# Schematic.net
KiCad netlist of a schematic drawn in Altium Designer
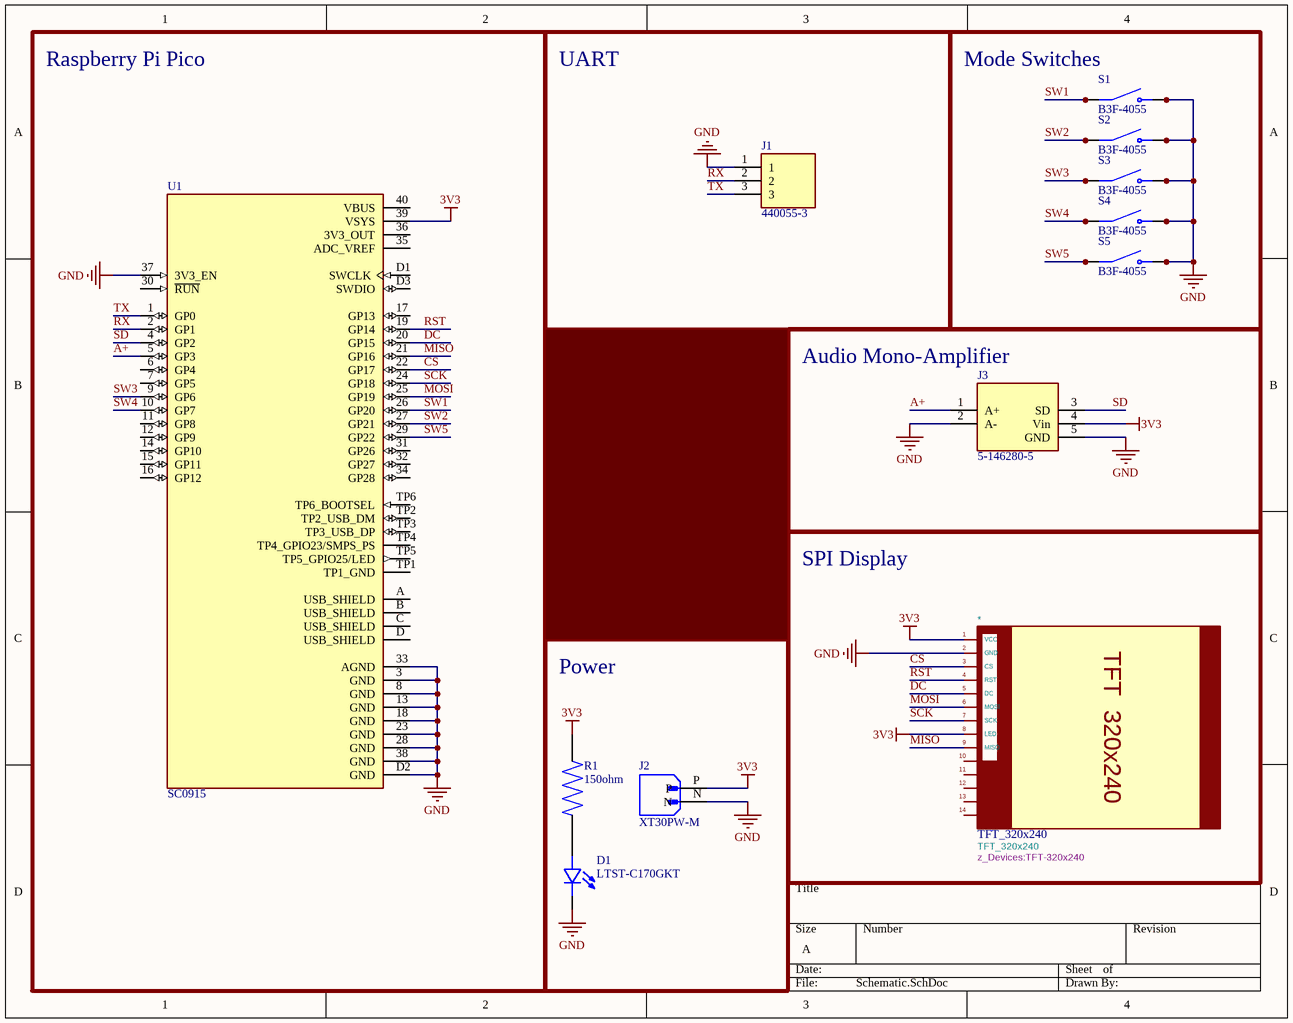
[diagram p0: Schematic.SchDoc]

(export (version "E")
  (design (tool "Eeschema 10.0.6"))
  (components
    (comp (ref "*")
      (value "TFT_320x240")
      (footprint "z_Devices:TFT-320x240")
      (fields (field (name "ALTIUM_VALUE") "TFT_320x240"))
      (libsource (lib "2.8inch") (part "TFT_320x240"))
    )
    (comp (ref "D1")
      (value "LTST-C170GKT")
      (footprint "LED_LTST-C170GKT")
      (description "Green 569nm LED Indication - Discrete 2.1V 0805 (2012 Metric)")
      (fields (field (name "MF") "Lite-On Inc."))
      (libsource (lib "LTST-C170GKT") (part "LTST-C170GKT"))
    )
    (comp (ref "J1")
      (value "440055-3")
      (footprint "TE_440055-3")
      (description "Connector Header Through Hole, Right Angle 3 position 0.079 _2.00mm_")
      (fields (field (name "MF") "TE Connectivity") (field (name "DIGI-KEY_PART_NUMBER") "A100044-ND"))
      (libsource (lib "440055-3") (part "440055-3"))
    )
    (comp (ref "J2")
      (value "XT30PW-M")
      (footprint "AMASS_XT30PW-M")
      (description "Socket; DC supply; XT30; male; PIN: 2; on PCBs; THT; Colour: yellow")
      (fields (field (name "MF") "AMASS"))
      (libsource (lib "XT30PW-M") (part "XT30PW-M"))
    )
    (comp (ref "J3")
      (value "5-146280-5")
      (footprint "TE_5-146280-5")
      (description "05 MODII HDR SRST B/A .100CL")
      (libsource (lib "5-146280-5 (2)") (part "5-146280-5"))
    )
    (comp (ref "R1")
      (value "150ohm")
      (footprint "RESC1005X40N")
      (description "150 Ohms Â±1% 0.063W, 1/16W Chip Resistor 0402 (1005 Metric) Moisture Resistant Thick Film")
      (fields (field (name "MF") "Yageo") (field (name "MP") "RC0402FR-07150RL"))
      (libsource (lib "RC0402FR-07150RL") (part "RC0402FR-07150RL"))
    )
    (comp (ref "S1")
      (value "B3F-4055")
      (footprint "SW_B3F-4055")
      (libsource (lib "B3F-4055") (part "B3F-4055"))
    )
    (comp (ref "S2")
      (value "B3F-4055")
      (footprint "SW_B3F-4055")
      (libsource (lib "B3F-4055") (part "B3F-4055"))
    )
    (comp (ref "S3")
      (value "B3F-4055")
      (footprint "SW_B3F-4055")
      (libsource (lib "B3F-4055") (part "B3F-4055"))
    )
    (comp (ref "S4")
      (value "B3F-4055")
      (footprint "SW_B3F-4055")
      (libsource (lib "B3F-4055") (part "B3F-4055"))
    )
    (comp (ref "S5")
      (value "B3F-4055")
      (footprint "SW_B3F-4055")
      (libsource (lib "B3F-4055") (part "B3F-4055"))
    )
    (comp (ref "U1")
      (value "SC0915")
      (footprint "MODULE_SC0915")
      (description "RP2040 Raspberry Pi Pico series ARMÂ® CortexÂ®-M0+ MCU 32-Bit Embedded Evaluation Board")
      (fields (field (name "MF") "Raspberry Pi"))
      (libsource (lib "SC0915") (part "SC0915"))
    )
  )
  (nets
    (net (code "1") (name "/A+") (class "Default")
      (node (ref "J3") (pin "1") (pinfunction "A+_1") (pintype "passive"))
      (node (ref "U1") (pin "5") (pinfunction "GP3_5") (pintype "bidirectional"))
    )
    (net (code "2") (name "/CS") (class "Default")
      (node (ref "*") (pin "3") (pinfunction "CS_3") (pintype "passive"))
      (node (ref "U1") (pin "22") (pinfunction "GP17_22") (pintype "bidirectional"))
    )
    (net (code "3") (name "/DC") (class "Default")
      (node (ref "*") (pin "5") (pinfunction "DC_5") (pintype "passive"))
      (node (ref "U1") (pin "20") (pinfunction "GP15_20") (pintype "bidirectional"))
    )
    (net (code "4") (name "/MISO") (class "Default")
      (node (ref "*") (pin "9") (pinfunction "MISO_9") (pintype "passive"))
      (node (ref "U1") (pin "21") (pinfunction "GP16_21") (pintype "bidirectional"))
    )
    (net (code "5") (name "/MOSI") (class "Default")
      (node (ref "*") (pin "6") (pinfunction "MOSI_6") (pintype "passive"))
      (node (ref "U1") (pin "25") (pinfunction "GP19_25") (pintype "bidirectional"))
    )
    (net (code "6") (name "/RST") (class "Default")
      (node (ref "*") (pin "4") (pinfunction "RST_4") (pintype "passive"))
      (node (ref "U1") (pin "19") (pinfunction "GP14_19") (pintype "bidirectional"))
    )
    (net (code "7") (name "/RX") (class "Default")
      (node (ref "J1") (pin "2") (pinfunction "2_2") (pintype "passive"))
      (node (ref "U1") (pin "2") (pinfunction "GP1_2") (pintype "bidirectional"))
    )
    (net (code "8") (name "/SCK") (class "Default")
      (node (ref "*") (pin "7") (pinfunction "SCK_7") (pintype "passive"))
      (node (ref "U1") (pin "24") (pinfunction "GP18_24") (pintype "bidirectional"))
    )
    (net (code "9") (name "/SD") (class "Default")
      (node (ref "J3") (pin "3") (pinfunction "SD_3") (pintype "passive"))
      (node (ref "U1") (pin "4") (pinfunction "GP2_4") (pintype "bidirectional"))
    )
    (net (code "10") (name "/SW1") (class "Default")
      (node (ref "S1") (pin "1") (pinfunction "COM_1") (pintype "passive"))
      (node (ref "S1") (pin "2") (pinfunction "COM_2") (pintype "passive"))
      (node (ref "U1") (pin "26") (pinfunction "GP20_26") (pintype "bidirectional"))
    )
    (net (code "11") (name "/SW2") (class "Default")
      (node (ref "S2") (pin "1") (pinfunction "COM_1") (pintype "passive"))
      (node (ref "S2") (pin "2") (pinfunction "COM_2") (pintype "passive"))
      (node (ref "U1") (pin "27") (pinfunction "GP21_27") (pintype "bidirectional"))
    )
    (net (code "12") (name "/SW3") (class "Default")
      (node (ref "S3") (pin "1") (pinfunction "COM_1") (pintype "passive"))
      (node (ref "S3") (pin "2") (pinfunction "COM_2") (pintype "passive"))
      (node (ref "U1") (pin "9") (pinfunction "GP6_9") (pintype "bidirectional"))
    )
    (net (code "13") (name "/SW4") (class "Default")
      (node (ref "S4") (pin "1") (pinfunction "COM_1") (pintype "passive"))
      (node (ref "S4") (pin "2") (pinfunction "COM_2") (pintype "passive"))
      (node (ref "U1") (pin "10") (pinfunction "GP7_10") (pintype "bidirectional"))
    )
    (net (code "14") (name "/SW5") (class "Default")
      (node (ref "S5") (pin "1") (pinfunction "COM_1") (pintype "passive"))
      (node (ref "S5") (pin "2") (pinfunction "COM_2") (pintype "passive"))
      (node (ref "U1") (pin "29") (pinfunction "GP22_29") (pintype "bidirectional"))
    )
    (net (code "15") (name "/TX") (class "Default")
      (node (ref "J1") (pin "3") (pinfunction "3_3") (pintype "passive"))
      (node (ref "U1") (pin "1") (pinfunction "GP0_1") (pintype "bidirectional"))
    )
    (net (code "16") (name "3V3") (class "Default")
      (node (ref "*") (pin "1") (pinfunction "VCC_1") (pintype "passive"))
      (node (ref "*") (pin "8") (pinfunction "LED_8") (pintype "passive"))
      (node (ref "J2") (pin "P") (pinfunction "P_P") (pintype "power_in"))
      (node (ref "J3") (pin "4") (pinfunction "Vin_4") (pintype "passive"))
      (node (ref "R1") (pin "1") (pinfunction "1_1") (pintype "passive"))
      (node (ref "U1") (pin "39") (pinfunction "VSYS_39") (pintype "power_in"))
    )
    (net (code "17") (name "GND") (class "Default")
      (node (ref "*") (pin "2") (pinfunction "GND_2") (pintype "passive"))
      (node (ref "D1") (pin "1") (pinfunction "C_1") (pintype "passive"))
      (node (ref "J1") (pin "1") (pinfunction "1_1") (pintype "passive"))
      (node (ref "J2") (pin "N") (pinfunction "N_N") (pintype "power_in"))
      (node (ref "J3") (pin "2") (pinfunction "A-_2") (pintype "passive"))
      (node (ref "J3") (pin "5") (pinfunction "GND_5") (pintype "passive"))
      (node (ref "S1") (pin "3") (pinfunction "NO_3") (pintype "passive"))
      (node (ref "S1") (pin "4") (pinfunction "NO_4") (pintype "passive"))
      (node (ref "S2") (pin "3") (pinfunction "NO_3") (pintype "passive"))
      (node (ref "S2") (pin "4") (pinfunction "NO_4") (pintype "passive"))
      (node (ref "S3") (pin "3") (pinfunction "NO_3") (pintype "passive"))
      (node (ref "S3") (pin "4") (pinfunction "NO_4") (pintype "passive"))
      (node (ref "S4") (pin "3") (pinfunction "NO_3") (pintype "passive"))
      (node (ref "S4") (pin "4") (pinfunction "NO_4") (pintype "passive"))
      (node (ref "S5") (pin "3") (pinfunction "NO_3") (pintype "passive"))
      (node (ref "S5") (pin "4") (pinfunction "NO_4") (pintype "passive"))
      (node (ref "U1") (pin "13") (pinfunction "GND_13") (pintype "power_in"))
      (node (ref "U1") (pin "18") (pinfunction "GND_18") (pintype "power_in"))
      (node (ref "U1") (pin "23") (pinfunction "GND_23") (pintype "power_in"))
      (node (ref "U1") (pin "28") (pinfunction "GND_28") (pintype "power_in"))
      (node (ref "U1") (pin "3") (pinfunction "GND_3") (pintype "power_in"))
      (node (ref "U1") (pin "33") (pinfunction "AGND_33") (pintype "power_in"))
      (node (ref "U1") (pin "37") (pinfunction "3V3_EN_37") (pintype "input"))
      (node (ref "U1") (pin "38") (pinfunction "GND_38") (pintype "power_in"))
      (node (ref "U1") (pin "8") (pinfunction "GND_8") (pintype "power_in"))
      (node (ref "U1") (pin "D2") (pinfunction "GND_D2") (pintype "power_in"))
    )
    (net (code "18") (name "Net-(D1-A)") (class "Default")
      (node (ref "D1") (pin "2") (pinfunction "A_2") (pintype "passive"))
      (node (ref "R1") (pin "2") (pinfunction "2_2") (pintype "passive"))
    )
    (net (code "19") (name "unconnected-(*-Pad10)") (class "Default")
      (node (ref "*") (pin "10") (pinfunction "10_10") (pintype "passive"))
    )
    (net (code "20") (name "unconnected-(*-Pad11)") (class "Default")
      (node (ref "*") (pin "11") (pinfunction "11_11") (pintype "passive"))
    )
    (net (code "21") (name "unconnected-(*-Pad12)") (class "Default")
      (node (ref "*") (pin "12") (pinfunction "12_12") (pintype "passive"))
    )
    (net (code "22") (name "unconnected-(*-Pad13)") (class "Default")
      (node (ref "*") (pin "13") (pinfunction "13_13") (pintype "passive"))
    )
    (net (code "23") (name "unconnected-(*-Pad14)") (class "Default")
      (node (ref "*") (pin "14") (pinfunction "14_14") (pintype "passive"))
    )
    (net (code "24") (name "unconnected-(U1-3V3_OUT-Pad36)") (class "Default")
      (node (ref "U1") (pin "36") (pinfunction "3V3_OUT_36") (pintype "power_in"))
    )
    (net (code "25") (name "unconnected-(U1-ADC_VREF-Pad35)") (class "Default")
      (node (ref "U1") (pin "35") (pinfunction "ADC_VREF_35") (pintype "power_in"))
    )
    (net (code "26") (name "unconnected-(U1-GP4-Pad6)") (class "Default")
      (node (ref "U1") (pin "6") (pinfunction "GP4_6") (pintype "bidirectional"))
    )
    (net (code "27") (name "unconnected-(U1-GP5-Pad7)") (class "Default")
      (node (ref "U1") (pin "7") (pinfunction "GP5_7") (pintype "bidirectional"))
    )
    (net (code "28") (name "unconnected-(U1-GP8-Pad11)") (class "Default")
      (node (ref "U1") (pin "11") (pinfunction "GP8_11") (pintype "bidirectional"))
    )
    (net (code "29") (name "unconnected-(U1-GP9-Pad12)") (class "Default")
      (node (ref "U1") (pin "12") (pinfunction "GP9_12") (pintype "bidirectional"))
    )
    (net (code "30") (name "unconnected-(U1-GP10-Pad14)") (class "Default")
      (node (ref "U1") (pin "14") (pinfunction "GP10_14") (pintype "bidirectional"))
    )
    (net (code "31") (name "unconnected-(U1-GP11-Pad15)") (class "Default")
      (node (ref "U1") (pin "15") (pinfunction "GP11_15") (pintype "bidirectional"))
    )
    (net (code "32") (name "unconnected-(U1-GP12-Pad16)") (class "Default")
      (node (ref "U1") (pin "16") (pinfunction "GP12_16") (pintype "bidirectional"))
    )
    (net (code "33") (name "unconnected-(U1-GP13-Pad17)") (class "Default")
      (node (ref "U1") (pin "17") (pinfunction "GP13_17") (pintype "bidirectional"))
    )
    (net (code "34") (name "unconnected-(U1-GP26-Pad31)") (class "Default")
      (node (ref "U1") (pin "31") (pinfunction "GP26_31") (pintype "bidirectional"))
    )
    (net (code "35") (name "unconnected-(U1-GP27-Pad32)") (class "Default")
      (node (ref "U1") (pin "32") (pinfunction "GP27_32") (pintype "bidirectional"))
    )
    (net (code "36") (name "unconnected-(U1-GP28-Pad34)") (class "Default")
      (node (ref "U1") (pin "34") (pinfunction "GP28_34") (pintype "bidirectional"))
    )
    (net (code "37") (name "unconnected-(U1-SWCLK-PadD1)") (class "Default")
      (node (ref "U1") (pin "D1") (pinfunction "SWCLK_D1") (pintype "input"))
    )
    (net (code "38") (name "unconnected-(U1-SWDIO-PadD3)") (class "Default")
      (node (ref "U1") (pin "D3") (pinfunction "SWDIO_D3") (pintype "bidirectional"))
    )
    (net (code "39") (name "unconnected-(U1-TP1_GND-PadTP1)") (class "Default")
      (node (ref "U1") (pin "TP1") (pinfunction "TP1_GND_TP1") (pintype "power_in"))
    )
    (net (code "40") (name "unconnected-(U1-TP2_USB_DM-PadTP2)") (class "Default")
      (node (ref "U1") (pin "TP2") (pinfunction "TP2_USB_DM_TP2") (pintype "bidirectional"))
    )
    (net (code "41") (name "unconnected-(U1-TP3_USB_DP-PadTP3)") (class "Default")
      (node (ref "U1") (pin "TP3") (pinfunction "TP3_USB_DP_TP3") (pintype "bidirectional"))
    )
    (net (code "42") (name "unconnected-(U1-TP4_GPIO23{slash}SMPS_PS-PadTP4)") (class "Default")
      (node (ref "U1") (pin "TP4") (pinfunction "TP4_GPIO23/SMPS_PS_TP4") (pintype "passive"))
    )
    (net (code "43") (name "unconnected-(U1-TP5_GPIO25{slash}LED-PadTP5)") (class "Default")
      (node (ref "U1") (pin "TP5") (pinfunction "TP5_GPIO25/LED_TP5") (pintype "output"))
    )
    (net (code "44") (name "unconnected-(U1-TP6_BOOTSEL-PadTP6)") (class "Default")
      (node (ref "U1") (pin "TP6") (pinfunction "TP6_BOOTSEL_TP6") (pintype "input"))
    )
    (net (code "45") (name "unconnected-(U1-USB_SHIELD-PadA)") (class "Default")
      (node (ref "U1") (pin "A") (pinfunction "USB_SHIELD_A") (pintype "power_in"))
    )
    (net (code "46") (name "unconnected-(U1-USB_SHIELD-PadB)") (class "Default")
      (node (ref "U1") (pin "B") (pinfunction "USB_SHIELD_B") (pintype "power_in"))
    )
    (net (code "47") (name "unconnected-(U1-USB_SHIELD-PadC)") (class "Default")
      (node (ref "U1") (pin "C") (pinfunction "USB_SHIELD_C") (pintype "power_in"))
    )
    (net (code "48") (name "unconnected-(U1-USB_SHIELD-PadD)") (class "Default")
      (node (ref "U1") (pin "D") (pinfunction "USB_SHIELD_D") (pintype "power_in"))
    )
    (net (code "49") (name "unconnected-(U1-VBUS-Pad40)") (class "Default")
      (node (ref "U1") (pin "40") (pinfunction "VBUS_40") (pintype "power_in"))
    )
    (net (code "50") (name "unconnected-(U1-~{RUN}-Pad30)") (class "Default")
      (node (ref "U1") (pin "30") (pinfunction "~{RUN}_30") (pintype "input"))
    )
  )
)
